# -2V5_DIST.net
KiCad netlist of a schematic drawn in Altium Designer
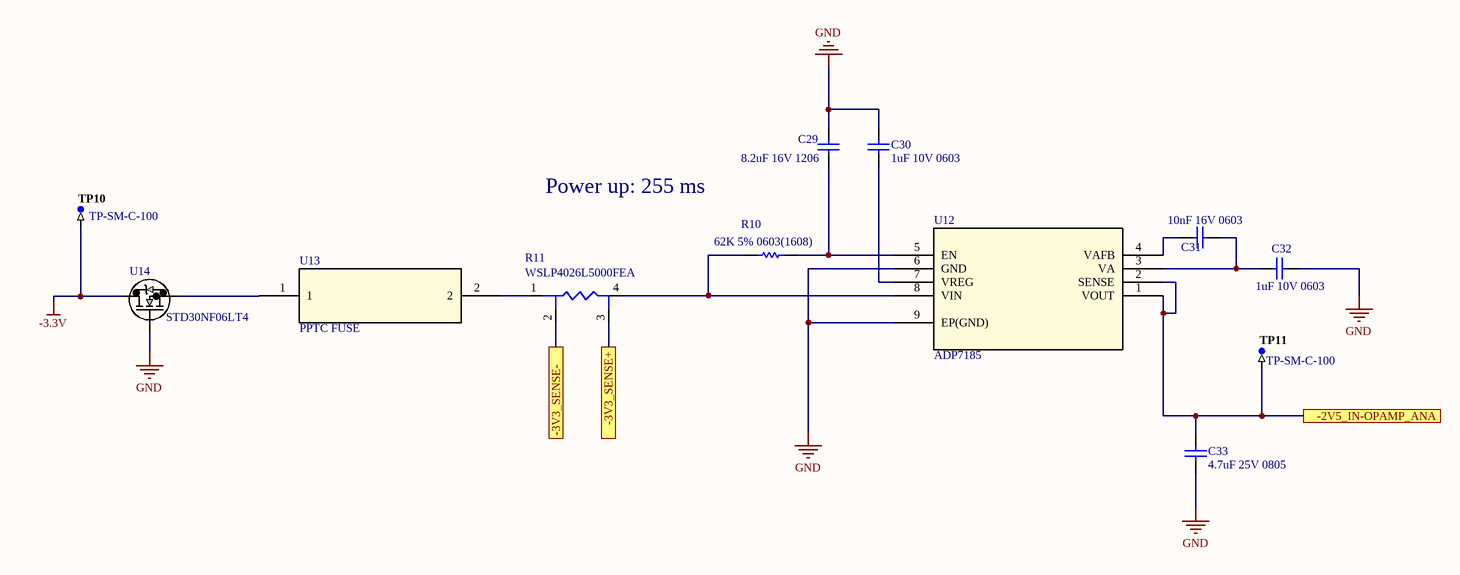
[diagram p0: -2V5_DIST.SchDoc]

(export (version "E")
  (design (tool "Eeschema 10.0.6"))
  (components
    (comp (ref "C29")
      (value "8.2uF 16V 1206")
      (footprint "CAPC1206(3216)190_N")
      (description "CAP 8.2uF 16V ±20% 1206 (3216 Metric) Thickness 1.9mm SMD")
      (fields (field (name "TOLERANCE") "Â±20%"))
      (libsource (lib "Altium Content Vault") (part "CAP"))
    )
    (comp (ref "C30")
      (value "1uF 10V 0603")
      (footprint "CAPC0603(1608)100_L")
      (description "CAP 1uF 10V ±20% 0603 (1608 Metric) Thickness 1mm SMD")
      (fields (field (name "TOLERANCE") "Â±20%"))
      (libsource (lib "Altium Content Vault") (part "CAP"))
    )
    (comp (ref "C31")
      (value "10nF 16V 0603")
      (footprint "CAPC0603(1608)100_L")
      (description "CAP 10nF 16V ±10% 0603 (1608 Metric) Thickness 1mm SMD")
      (fields (field (name "TOLERANCE") "Â±10%"))
      (libsource (lib "Altium Content Vault") (part "CAP"))
    )
    (comp (ref "C32")
      (value "1uF 10V 0603")
      (footprint "CAPC0603(1608)100_L")
      (description "CAP 1uF 10V ±20% 0603 (1608 Metric) Thickness 1mm SMD")
      (fields (field (name "TOLERANCE") "Â±20%"))
      (libsource (lib "Altium Content Vault") (part "CAP"))
    )
    (comp (ref "C33")
      (value "4.7uF 25V 0805")
      (footprint "CAPC0805(2012)145_L")
      (description "CAP 4.7uF 25V ±10% 0805 (2012 Metric) Thickness 1.45mm SMD")
      (fields (field (name "TOLERANCE") "Â±10%"))
      (libsource (lib "Altium Content Vault") (part "CAP"))
    )
    (comp (ref "R10")
      (value "62K 5% 0603(1608)")
      (footprint "RESC0603(1608)_L")
      (description "62K 0.1W 5% 0603 (1608 Metric)  SMD")
      (fields (field (name "POWER") "0.1 W") (field (name "TOLERANCE") "5 %"))
      (libsource (lib "Altium Content Vault") (part "RES"))
    )
    (comp (ref "R11")
      (value "WSLP4026L5000FEA")
      (description "Current Sense Resistors - SMD 7watt .0005ohm 1%")
      (libsource (lib "WSLP4026L5000FEA") (part "WSLP4026L5000FEA"))
    )
    (comp (ref "TP10")
      (value "TP-SM-C-100")
      (footprint "TP-SM-C-100")
      (description "Test Point, Surface Mount, Circular, Pad Diameter 1 mm")
      (fields (field (name "MANUFACTURER") "No Vendor"))
      (libsource (lib "Altium Content Vault") (part "TP-SM"))
    )
    (comp (ref "TP11")
      (value "TP-SM-C-100")
      (footprint "TP-SM-C-100")
      (description "Test Point, Surface Mount, Circular, Pad Diameter 1 mm")
      (fields (field (name "MANUFACTURER") "No Vendor"))
      (libsource (lib "Altium Content Vault") (part "TP-SM"))
    )
    (comp (ref "U12")
      (value "ADP7185")
      (footprint "CP_8_27")
      (description "LDO Voltage Regulators -500mA Ult low noise High Psrr negative")
      (fields (field (name "MANUFACTURER_PART_NUMBER") "ADP7185ACPZN1.0-R7"))
      (libsource (lib "ADP7185ACPZN1.0-R7") (part "ADP7185ACPZN1.0-"))
    )
    (comp (ref "U13")
      (value "PPTC FUSE")
      (footprint "0ZCF")
      (description "Resettable Fuses - PPTC")
      (fields (field (name "MANUFACTURER_PART_NUMBER") "0ZCF0250FF2C"))
      (libsource (lib "0ZCF0250FF2C") (part "0ZCF0250FF2C"))
    )
    (comp (ref "U14")
      (value "STD30NF06LT4")
      (footprint "DPAK")
      (libsource (lib "STD30N6LF6AG") (part "STD30NF06LT4"))
    )
  )
  (nets
    (net (code "1") (name "-3.3V") (class "Default")
      (node (ref "TP10") (pin "1") (pinfunction "1_1") (pintype "input"))
      (node (ref "U14") (pin "2") (pinfunction "D_2") (pintype "passive"))
    )
    (net (code "2") (name "/-2V5_IN-OPAMP_ANA") (class "Default")
      (node (ref "C33") (pin "2") (pinfunction "2_2") (pintype "passive"))
      (node (ref "TP11") (pin "1") (pinfunction "1_1") (pintype "input"))
      (node (ref "U12") (pin "1") (pinfunction "VOUT_1") (pintype "passive"))
      (node (ref "U12") (pin "2") (pinfunction "SENSE_2") (pintype "passive"))
    )
    (net (code "3") (name "/-3V3_SENSE+") (class "Default") (node (ref "R11") (pin "3") (pintype "passive")))
    (net (code "4") (name "/-3V3_SENSE-") (class "Default") (node (ref "R11") (pin "2") (pintype "passive")))
    (net (code "5") (name "GND") (class "Default")
      (node (ref "C29") (pin "2") (pinfunction "2_2") (pintype "passive"))
      (node (ref "C30") (pin "2") (pinfunction "2_2") (pintype "passive"))
      (node (ref "C32") (pin "2") (pinfunction "2_2") (pintype "passive"))
      (node (ref "C33") (pin "1") (pinfunction "1_1") (pintype "passive"))
      (node (ref "U12") (pin "6") (pinfunction "GND_6") (pintype "passive"))
      (node (ref "U12") (pin "9") (pinfunction "EP(GND)_9") (pintype "passive"))
      (node (ref "U14") (pin "1") (pinfunction "G_1") (pintype "passive"))
    )
    (net (code "6") (name "Net-(R11-Pad1)") (class "Default")
      (node (ref "R11") (pin "1") (pintype "passive"))
      (node (ref "U13") (pin "2") (pinfunction "2_2") (pintype "passive"))
    )
    (net (code "7") (name "Net-(U12-EN)") (class "Default")
      (node (ref "C29") (pin "1") (pinfunction "1_1") (pintype "passive"))
      (node (ref "R10") (pin "2") (pinfunction "2_2") (pintype "passive"))
      (node (ref "U12") (pin "5") (pinfunction "EN_5") (pintype "passive"))
    )
    (net (code "8") (name "Net-(U12-VA)") (class "Default")
      (node (ref "C31") (pin "1") (pinfunction "1_1") (pintype "passive"))
      (node (ref "C32") (pin "1") (pinfunction "1_1") (pintype "passive"))
      (node (ref "U12") (pin "3") (pinfunction "VA_3") (pintype "passive"))
    )
    (net (code "9") (name "Net-(U12-VAFB)") (class "Default")
      (node (ref "C31") (pin "2") (pinfunction "2_2") (pintype "passive"))
      (node (ref "U12") (pin "4") (pinfunction "VAFB_4") (pintype "passive"))
    )
    (net (code "10") (name "Net-(U12-VIN)") (class "Default")
      (node (ref "R10") (pin "1") (pinfunction "1_1") (pintype "passive"))
      (node (ref "R11") (pin "4") (pintype "passive"))
      (node (ref "U12") (pin "8") (pinfunction "VIN_8") (pintype "passive"))
    )
    (net (code "11") (name "Net-(U12-VREG)") (class "Default")
      (node (ref "C30") (pin "1") (pinfunction "1_1") (pintype "passive"))
      (node (ref "U12") (pin "7") (pinfunction "VREG_7") (pintype "passive"))
    )
    (net (code "12") (name "Net-(U14-S)") (class "Default")
      (node (ref "U13") (pin "1") (pinfunction "1_1") (pintype "passive"))
      (node (ref "U14") (pin "3") (pinfunction "S_3") (pintype "passive"))
    )
  )
)
